# power_supply.net
KiCad netlist of a schematic drawn in Altium Designer
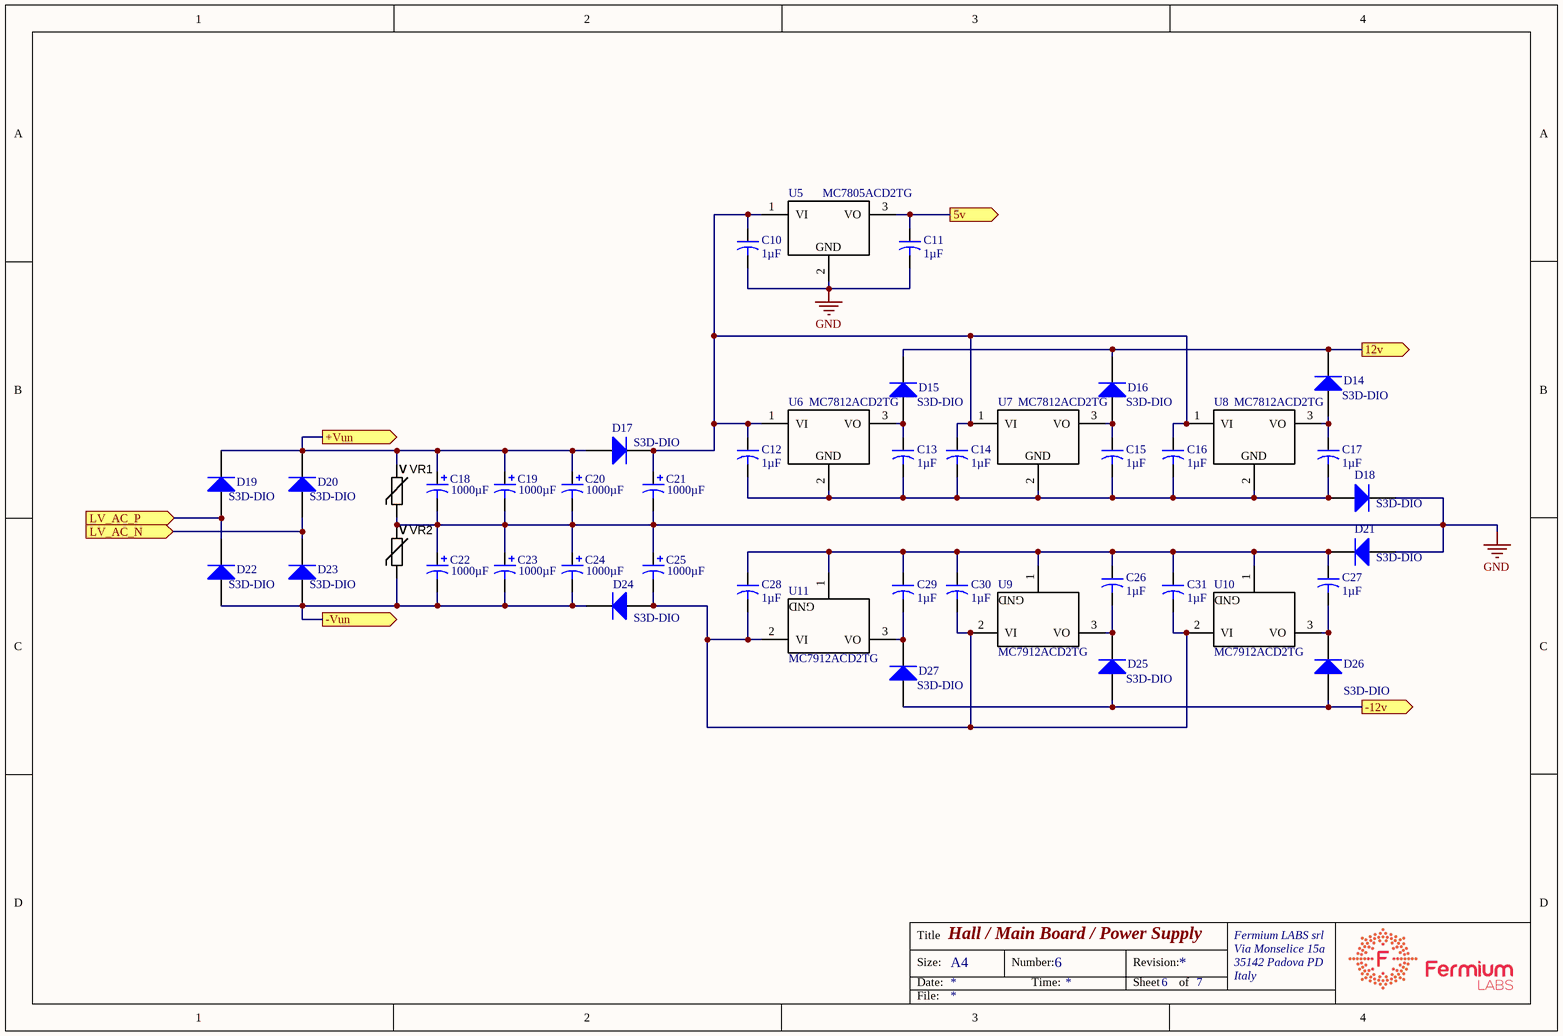
[diagram p0: power_supply.SchDoc]

(export (version "E")
  (design (tool "Eeschema 10.0.6"))
  (components
    (comp (ref "C10")
      (value "~")
      (footprint "Passives:CAP 0805/2012")
      (description "Capacitor")
      (fields
        (field (name "MANUFACTURER") "SAMSUNG")
        (field (name "MANUFACTURER PART NUMBER") "CL21B105KAFNNNE")
        (field (name "CAPACITANCE") "1µF")
        (field (name "PUBLISHER") "Altium Limited")
      )
      (libsource (lib "Miscellaneous Devices") (part "Cap2"))
    )
    (comp (ref "C11")
      (value "~")
      (footprint "Passives:CAP 0805/2012")
      (description "Capacitor")
      (fields
        (field (name "MANUFACTURER") "SAMSUNG")
        (field (name "MANUFACTURER PART NUMBER") "CL21B105KAFNNNE")
        (field (name "CAPACITANCE") "1µF")
        (field (name "PUBLISHER") "Altium Limited")
      )
      (libsource (lib "Miscellaneous Devices") (part "Cap2"))
    )
    (comp (ref "C12")
      (value "~")
      (footprint "Passives:CAP 0805/2012")
      (description "Capacitor")
      (fields
        (field (name "MANUFACTURER") "SAMSUNG")
        (field (name "MANUFACTURER PART NUMBER") "CL21B105KAFNNNE")
        (field (name "CAPACITANCE") "1µF")
        (field (name "PUBLISHER") "Altium Limited")
      )
      (libsource (lib "Miscellaneous Devices") (part "Cap2"))
    )
    (comp (ref "C13")
      (value "~")
      (footprint "Passives:CAP 0805/2012")
      (description "Capacitor")
      (fields
        (field (name "MANUFACTURER") "SAMSUNG")
        (field (name "MANUFACTURER PART NUMBER") "CL21B105KAFNNNE")
        (field (name "CAPACITANCE") "1µF")
        (field (name "PUBLISHER") "Altium Limited")
      )
      (libsource (lib "Miscellaneous Devices") (part "Cap2"))
    )
    (comp (ref "C14")
      (value "~")
      (footprint "Passives:CAP 0805/2012")
      (description "Capacitor")
      (fields
        (field (name "MANUFACTURER") "SAMSUNG")
        (field (name "MANUFACTURER PART NUMBER") "CL21B105KAFNNNE")
        (field (name "CAPACITANCE") "1µF")
        (field (name "PUBLISHER") "Altium Limited")
      )
      (libsource (lib "Miscellaneous Devices") (part "Cap2"))
    )
    (comp (ref "C15")
      (value "~")
      (footprint "Passives:CAP 0805/2012")
      (description "Capacitor")
      (fields
        (field (name "MANUFACTURER") "SAMSUNG")
        (field (name "MANUFACTURER PART NUMBER") "CL21B105KAFNNNE")
        (field (name "CAPACITANCE") "1µF")
        (field (name "PUBLISHER") "Altium Limited")
      )
      (libsource (lib "Miscellaneous Devices") (part "Cap2"))
    )
    (comp (ref "C16")
      (value "~")
      (footprint "Passives:CAP 0805/2012")
      (description "Capacitor")
      (fields
        (field (name "MANUFACTURER") "SAMSUNG")
        (field (name "MANUFACTURER PART NUMBER") "CL21B105KAFNNNE")
        (field (name "CAPACITANCE") "1µF")
        (field (name "PUBLISHER") "Altium Limited")
      )
      (libsource (lib "Miscellaneous Devices") (part "Cap2"))
    )
    (comp (ref "C17")
      (value "~")
      (footprint "Passives:CAP 0805/2012")
      (description "Capacitor")
      (fields
        (field (name "MANUFACTURER") "SAMSUNG")
        (field (name "MANUFACTURER PART NUMBER") "CL21B105KAFNNNE")
        (field (name "CAPACITANCE") "1µF")
        (field (name "PUBLISHER") "Altium Limited")
      )
      (libsource (lib "Miscellaneous Devices") (part "Cap2"))
    )
    (comp (ref "C18")
      (value "~")
      (footprint "PBL - THD Packages:CAPE5.0mm")
      (description "capacitor , electrolytic")
      (fields
        (field (name "MANUFACTURER") "United Chemi-Con")
        (field (name "MANUFACTURER PART NUMBER") "EKYB250ELL102MJ20S")
        (field (name "CAPACITANCE") "1000µF")
      )
      (libsource (lib "Miscellaneous Devices") (part "Cap Pol1"))
    )
    (comp (ref "C19")
      (value "~")
      (footprint "PBL - THD Packages:CAPE5.0mm")
      (description "capacitor , electrolytic")
      (fields
        (field (name "MANUFACTURER") "United Chemi-Con")
        (field (name "MANUFACTURER PART NUMBER") "EKYB250ELL102MJ20S")
        (field (name "CAPACITANCE") "1000µF")
      )
      (libsource (lib "Miscellaneous Devices") (part "Cap Pol1"))
    )
    (comp (ref "C20")
      (value "~")
      (footprint "PBL - THD Packages:CAPE5.0mm")
      (description "capacitor , electrolytic")
      (fields
        (field (name "MANUFACTURER") "United Chemi-Con")
        (field (name "MANUFACTURER PART NUMBER") "EKYB250ELL102MJ20S")
        (field (name "CAPACITANCE") "1000µF")
      )
      (libsource (lib "Miscellaneous Devices") (part "Cap Pol1"))
    )
    (comp (ref "C21")
      (value "~")
      (footprint "PBL - THD Packages:CAPE5.0mm")
      (description "capacitor , electrolytic")
      (fields
        (field (name "MANUFACTURER") "United Chemi-Con")
        (field (name "MANUFACTURER PART NUMBER") "EKYB250ELL102MJ20S")
        (field (name "CAPACITANCE") "1000µF")
      )
      (libsource (lib "Miscellaneous Devices") (part "Cap Pol1"))
    )
    (comp (ref "C22")
      (value "~")
      (footprint "PBL - THD Packages:CAPE5.0mm")
      (description "capacitor , electrolytic")
      (fields
        (field (name "MANUFACTURER") "United Chemi-Con")
        (field (name "MANUFACTURER PART NUMBER") "EKYB250ELL102MJ20S")
        (field (name "CAPACITANCE") "1000µF")
      )
      (libsource (lib "Miscellaneous Devices") (part "Cap Pol1"))
    )
    (comp (ref "C23")
      (value "~")
      (footprint "PBL - THD Packages:CAPE5.0mm")
      (description "capacitor , electrolytic")
      (fields
        (field (name "MANUFACTURER") "United Chemi-Con")
        (field (name "MANUFACTURER PART NUMBER") "EKYB250ELL102MJ20S")
        (field (name "CAPACITANCE") "1000µF")
      )
      (libsource (lib "Miscellaneous Devices") (part "Cap Pol1"))
    )
    (comp (ref "C24")
      (value "~")
      (footprint "PBL - THD Packages:CAPE5.0mm")
      (description "capacitor , electrolytic")
      (fields
        (field (name "MANUFACTURER") "United Chemi-Con")
        (field (name "MANUFACTURER PART NUMBER") "EKYB250ELL102MJ20S")
        (field (name "CAPACITANCE") "1000µF")
      )
      (libsource (lib "Miscellaneous Devices") (part "Cap Pol1"))
    )
    (comp (ref "C25")
      (value "~")
      (footprint "PBL - THD Packages:CAPE5.0mm")
      (description "capacitor , electrolytic")
      (fields
        (field (name "MANUFACTURER") "United Chemi-Con")
        (field (name "MANUFACTURER PART NUMBER") "EKYB250ELL102MJ20S")
        (field (name "CAPACITANCE") "1000µF")
      )
      (libsource (lib "Miscellaneous Devices") (part "Cap Pol1"))
    )
    (comp (ref "C26")
      (value "~")
      (footprint "Passives:CAP 0805/2012")
      (description "Capacitor")
      (fields
        (field (name "MANUFACTURER") "SAMSUNG")
        (field (name "MANUFACTURER PART NUMBER") "CL21B105KAFNNNE")
        (field (name "CAPACITANCE") "1µF")
        (field (name "PUBLISHER") "Altium Limited")
      )
      (libsource (lib "Miscellaneous Devices") (part "Cap2"))
    )
    (comp (ref "C27")
      (value "~")
      (footprint "Passives:CAP 0805/2012")
      (description "Capacitor")
      (fields
        (field (name "MANUFACTURER") "SAMSUNG")
        (field (name "MANUFACTURER PART NUMBER") "CL21B105KAFNNNE")
        (field (name "CAPACITANCE") "1µF")
        (field (name "PUBLISHER") "Altium Limited")
      )
      (libsource (lib "Miscellaneous Devices") (part "Cap2"))
    )
    (comp (ref "C28")
      (value "~")
      (footprint "Passives:CAP 0805/2012")
      (description "Capacitor")
      (fields
        (field (name "MANUFACTURER") "SAMSUNG")
        (field (name "MANUFACTURER PART NUMBER") "CL21B105KAFNNNE")
        (field (name "CAPACITANCE") "1µF")
        (field (name "PUBLISHER") "Altium Limited")
      )
      (libsource (lib "Miscellaneous Devices") (part "Cap2"))
    )
    (comp (ref "C29")
      (value "~")
      (footprint "Passives:CAP 0805/2012")
      (description "Capacitor")
      (fields
        (field (name "MANUFACTURER") "SAMSUNG")
        (field (name "MANUFACTURER PART NUMBER") "CL21B105KAFNNNE")
        (field (name "CAPACITANCE") "1µF")
        (field (name "PUBLISHER") "Altium Limited")
      )
      (libsource (lib "Miscellaneous Devices") (part "Cap2"))
    )
    (comp (ref "C30")
      (value "~")
      (footprint "Passives:CAP 0805/2012")
      (description "Capacitor")
      (fields
        (field (name "MANUFACTURER") "SAMSUNG")
        (field (name "MANUFACTURER PART NUMBER") "CL21B105KAFNNNE")
        (field (name "CAPACITANCE") "1µF")
        (field (name "PUBLISHER") "Altium Limited")
      )
      (libsource (lib "Miscellaneous Devices") (part "Cap2"))
    )
    (comp (ref "C31")
      (value "~")
      (footprint "Passives:CAP 0805/2012")
      (description "Capacitor")
      (fields
        (field (name "MANUFACTURER") "SAMSUNG")
        (field (name "MANUFACTURER PART NUMBER") "CL21B105KAFNNNE")
        (field (name "CAPACITANCE") "1µF")
        (field (name "PUBLISHER") "Altium Limited")
      )
      (libsource (lib "Miscellaneous Devices") (part "Cap2"))
    )
    (comp (ref "D14")
      (value "~")
      (footprint "DIODE-SMC")
      (description "Diode rectifier 1A")
      (fields
        (field (name "SUPPLIER PART NUMBER 1") "S3D-DIO")
        (field (name "MANUFACTURER") "DIOTEC SEMICONDUCTOR")
        (field (name "MANUFACTURER PART NUMBER") "S3D")
      )
      (libsource (lib "Miscellaneous Devices") (part "Diode 1N4007"))
    )
    (comp (ref "D15")
      (value "~")
      (footprint "DIODE-SMC")
      (description "Diode rectifier 1A")
      (fields
        (field (name "SUPPLIER PART NUMBER 1") "S3D-DIO")
        (field (name "MANUFACTURER") "DIOTEC SEMICONDUCTOR")
        (field (name "MANUFACTURER PART NUMBER") "S3D")
      )
      (libsource (lib "Miscellaneous Devices") (part "Diode 1N4007"))
    )
    (comp (ref "D16")
      (value "~")
      (footprint "DIODE-SMC")
      (description "Diode rectifier 1A")
      (fields
        (field (name "SUPPLIER PART NUMBER 1") "S3D-DIO")
        (field (name "MANUFACTURER") "DIOTEC SEMICONDUCTOR")
        (field (name "MANUFACTURER PART NUMBER") "S3D")
      )
      (libsource (lib "Miscellaneous Devices") (part "Diode 1N4007"))
    )
    (comp (ref "D17")
      (value "~")
      (footprint "DIODE-SMC")
      (description "Diode rectifier 1A")
      (fields
        (field (name "SUPPLIER PART NUMBER 1") "S3D-DIO")
        (field (name "MANUFACTURER") "DIOTEC SEMICONDUCTOR")
        (field (name "MANUFACTURER PART NUMBER") "S3D")
      )
      (libsource (lib "Miscellaneous Devices") (part "Diode 1N4007"))
    )
    (comp (ref "D18")
      (value "~")
      (footprint "DIODE-SMC")
      (description "Diode rectifier 1A")
      (fields
        (field (name "SUPPLIER PART NUMBER 1") "S3D-DIO")
        (field (name "MANUFACTURER") "DIOTEC SEMICONDUCTOR")
        (field (name "MANUFACTURER PART NUMBER") "S3D")
      )
      (libsource (lib "Miscellaneous Devices") (part "Diode 1N4007"))
    )
    (comp (ref "D19")
      (value "~")
      (footprint "DIODE-SMC")
      (description "Diode rectifier 1A")
      (fields
        (field (name "SUPPLIER PART NUMBER 1") "S3D-DIO")
        (field (name "MANUFACTURER") "DIOTEC SEMICONDUCTOR")
        (field (name "MANUFACTURER PART NUMBER") "S3D")
      )
      (libsource (lib "Miscellaneous Devices") (part "Diode 1N4007"))
    )
    (comp (ref "D20")
      (value "~")
      (footprint "DIODE-SMC")
      (description "Diode rectifier 1A")
      (fields
        (field (name "SUPPLIER PART NUMBER 1") "S3D-DIO")
        (field (name "MANUFACTURER") "DIOTEC SEMICONDUCTOR")
        (field (name "MANUFACTURER PART NUMBER") "S3D")
      )
      (libsource (lib "Miscellaneous Devices") (part "Diode 1N4007"))
    )
    (comp (ref "D21")
      (value "~")
      (footprint "DIODE-SMC")
      (description "Diode rectifier 1A")
      (fields
        (field (name "SUPPLIER PART NUMBER 1") "S3D-DIO")
        (field (name "MANUFACTURER") "DIOTEC SEMICONDUCTOR")
        (field (name "MANUFACTURER PART NUMBER") "S3D")
      )
      (libsource (lib "Miscellaneous Devices") (part "Diode 1N4007"))
    )
    (comp (ref "D22")
      (value "~")
      (footprint "DIODE-SMC")
      (description "Diode rectifier 1A")
      (fields
        (field (name "SUPPLIER PART NUMBER 1") "S3D-DIO")
        (field (name "MANUFACTURER") "DIOTEC SEMICONDUCTOR")
        (field (name "MANUFACTURER PART NUMBER") "S3D")
      )
      (libsource (lib "Miscellaneous Devices") (part "Diode 1N4007"))
    )
    (comp (ref "D23")
      (value "~")
      (footprint "DIODE-SMC")
      (description "Diode rectifier 1A")
      (fields
        (field (name "SUPPLIER PART NUMBER 1") "S3D-DIO")
        (field (name "MANUFACTURER") "DIOTEC SEMICONDUCTOR")
        (field (name "MANUFACTURER PART NUMBER") "S3D")
      )
      (libsource (lib "Miscellaneous Devices") (part "Diode 1N4007"))
    )
    (comp (ref "D24")
      (value "~")
      (footprint "DIODE-SMC")
      (description "Diode rectifier 1A")
      (fields
        (field (name "SUPPLIER PART NUMBER 1") "S3D-DIO")
        (field (name "MANUFACTURER") "DIOTEC SEMICONDUCTOR")
        (field (name "MANUFACTURER PART NUMBER") "S3D")
      )
      (libsource (lib "Miscellaneous Devices") (part "Diode 1N4007"))
    )
    (comp (ref "D25")
      (value "~")
      (footprint "DIODE-SMC")
      (description "Diode rectifier 1A")
      (fields
        (field (name "SUPPLIER PART NUMBER 1") "S3D-DIO")
        (field (name "MANUFACTURER") "DIOTEC SEMICONDUCTOR")
        (field (name "MANUFACTURER PART NUMBER") "S3D")
      )
      (libsource (lib "Miscellaneous Devices") (part "Diode 1N4007"))
    )
    (comp (ref "D26")
      (value "~")
      (footprint "DIODE-SMC")
      (description "Diode rectifier 1A")
      (fields
        (field (name "SUPPLIER PART NUMBER 1") "S3D-DIO")
        (field (name "MANUFACTURER") "DIOTEC SEMICONDUCTOR")
        (field (name "MANUFACTURER PART NUMBER") "S3D")
      )
      (libsource (lib "Miscellaneous Devices") (part "Diode 1N4007"))
    )
    (comp (ref "D27")
      (value "~")
      (footprint "DIODE-SMC")
      (description "Diode rectifier 1A")
      (fields
        (field (name "SUPPLIER PART NUMBER 1") "S3D-DIO")
        (field (name "MANUFACTURER") "DIOTEC SEMICONDUCTOR")
        (field (name "MANUFACTURER PART NUMBER") "S3D")
      )
      (libsource (lib "Miscellaneous Devices") (part "Diode 1N4007"))
    )
    (comp (ref "U5")
      (value "~")
      (footprint "PBL - SMD Packages:D2PAK-3")
      (description "Voltage regulator, 5V")
      (fields
        (field (name "SUPPLIER PART NUMBER 1") "MC7805ACD2TG")
        (field (name "MANUFACTURER") "ON SEMICONDUCTOR")
        (field (name "MANUFACTURER PART NUMBER") "MC7805ACD2TG")
      )
      (libsource (lib "vh_altium_library") (part "L7805-TO220"))
    )
    (comp (ref "U6")
      (value "~")
      (footprint "PBL - SMD Packages:D2PAK-3")
      (description "Voltage regulator, 15V")
      (fields
        (field (name "SUPPLIER PART NUMBER 1") "MC7812ACD2TG")
        (field (name "MANUFACTURER") "ON SEMICONDUCTOR")
        (field (name "MANUFACTURER PART NUMBER") "MC7812ACD2TG")
      )
      (libsource (lib "vh_altium_library") (part "L7815-TO220"))
    )
    (comp (ref "U7")
      (value "~")
      (footprint "PBL - SMD Packages:D2PAK-3")
      (description "Voltage regulator, 15V")
      (fields
        (field (name "SUPPLIER PART NUMBER 1") "MC7812ACD2TG")
        (field (name "MANUFACTURER") "ON SEMICONDUCTOR")
        (field (name "MANUFACTURER PART NUMBER") "MC7812ACD2TG")
      )
      (libsource (lib "vh_altium_library") (part "L7815-TO220"))
    )
    (comp (ref "U8")
      (value "~")
      (footprint "PBL - SMD Packages:D2PAK-3")
      (description "Voltage regulator, 15V")
      (fields
        (field (name "SUPPLIER PART NUMBER 1") "MC7812ACD2TG")
        (field (name "MANUFACTURER") "ON SEMICONDUCTOR")
        (field (name "MANUFACTURER PART NUMBER") "MC7812ACD2TG")
      )
      (libsource (lib "vh_altium_library") (part "L7815-TO220"))
    )
    (comp (ref "U9")
      (value "~")
      (footprint "PBL - SMD Packages:D2PAK-3")
      (description "Voltage regulator-15.0V")
      (fields
        (field (name "SUPPLIER PART NUMBER 1") "MC7912ACD2TG")
        (field (name "MANUFACTURER") "ON SEMICONDUCTOR")
        (field (name "MANUFACTURER PART NUMBER") "MC7912ACD2TG")
      )
      (libsource (lib "vh_altium_library") (part "L7915-TO220"))
    )
    (comp (ref "U10")
      (value "~")
      (footprint "PBL - SMD Packages:D2PAK-3")
      (description "Voltage regulator-15.0V")
      (fields
        (field (name "SUPPLIER PART NUMBER 1") "MC7912ACD2TG")
        (field (name "MANUFACTURER") "ON SEMICONDUCTOR")
        (field (name "MANUFACTURER PART NUMBER") "MC7912ACD2TG")
      )
      (libsource (lib "vh_altium_library") (part "L7915-TO220"))
    )
    (comp (ref "U11")
      (value "~")
      (footprint "PBL - SMD Packages:D2PAK-3")
      (description "Voltage regulator-15.0V")
      (fields
        (field (name "SUPPLIER PART NUMBER 1") "MC7912ACD2TG")
        (field (name "MANUFACTURER") "ON SEMICONDUCTOR")
        (field (name "MANUFACTURER PART NUMBER") "MC7912ACD2TG")
      )
      (libsource (lib "vh_altium_library") (part "L7915-TO220"))
    )
    (comp (ref "VR1")
      (value "~")
      (footprint "CAP 1206/3216 - 1.8MM")
      (description "Varistor")
      (fields
        (field (name "MANUFACTURER") "EPCOS")
        (field (name "MANUFACTURER PART NUMBER") "B72520T0250K062")
      )
      (libsource (lib "PBL - Fuses and Protection") (part "Varistor_MOV"))
    )
    (comp (ref "VR2")
      (value "~")
      (footprint "CAP 1206/3216 - 1.8MM")
      (description "Varistor")
      (fields
        (field (name "MANUFACTURER") "EPCOS")
        (field (name "MANUFACTURER PART NUMBER") "B72520T0250K062")
      )
      (libsource (lib "PBL - Fuses and Protection") (part "Varistor_MOV"))
    )
  )
  (nets
    (net (code "1") (name "/+Vun") (class "Default")
      (node (ref "C18") (pin "1") (pinfunction "1_1") (pintype "passive"))
      (node (ref "C19") (pin "1") (pinfunction "1_1") (pintype "passive"))
      (node (ref "C20") (pin "1") (pinfunction "1_1") (pintype "passive"))
      (node (ref "D17") (pin "A") (pinfunction "A_A") (pintype "passive"))
      (node (ref "D19") (pin "K") (pinfunction "K_K") (pintype "passive"))
      (node (ref "D20") (pin "K") (pinfunction "K_K") (pintype "passive"))
      (node (ref "VR1") (pin "1") (pinfunction "1_1") (pintype "passive"))
    )
    (net (code "2") (name "/-12v") (class "Default")
      (node (ref "D25") (pin "A") (pinfunction "A_A") (pintype "passive"))
      (node (ref "D26") (pin "A") (pinfunction "A_A") (pintype "passive"))
      (node (ref "D27") (pin "A") (pinfunction "A_A") (pintype "passive"))
    )
    (net (code "3") (name "/-Vun") (class "Default")
      (node (ref "C22") (pin "2") (pinfunction "2_2") (pintype "passive"))
      (node (ref "C23") (pin "2") (pinfunction "2_2") (pintype "passive"))
      (node (ref "C24") (pin "2") (pinfunction "2_2") (pintype "passive"))
      (node (ref "D22") (pin "A") (pinfunction "A_A") (pintype "passive"))
      (node (ref "D23") (pin "A") (pinfunction "A_A") (pintype "passive"))
      (node (ref "D24") (pin "K") (pinfunction "K_K") (pintype "passive"))
      (node (ref "VR2") (pin "2") (pinfunction "2_2") (pintype "passive"))
    )
    (net (code "4") (name "/5v") (class "Default")
      (node (ref "C11") (pin "1") (pinfunction "1_1") (pintype "passive"))
      (node (ref "U5") (pin "3") (pinfunction "VO_3") (pintype "passive"))
    )
    (net (code "5") (name "/12v") (class "Default")
      (node (ref "D14") (pin "K") (pinfunction "K_K") (pintype "passive"))
      (node (ref "D15") (pin "K") (pinfunction "K_K") (pintype "passive"))
      (node (ref "D16") (pin "K") (pinfunction "K_K") (pintype "passive"))
    )
    (net (code "6") (name "/LV_AC_N") (class "Default")
      (node (ref "D20") (pin "A") (pinfunction "A_A") (pintype "passive"))
      (node (ref "D23") (pin "K") (pinfunction "K_K") (pintype "passive"))
    )
    (net (code "7") (name "/LV_AC_P") (class "Default")
      (node (ref "D19") (pin "A") (pinfunction "A_A") (pintype "passive"))
      (node (ref "D22") (pin "K") (pinfunction "K_K") (pintype "passive"))
    )
    (net (code "8") (name "GND") (class "Default")
      (node (ref "C10") (pin "2") (pinfunction "2_2") (pintype "passive"))
      (node (ref "C11") (pin "2") (pinfunction "2_2") (pintype "passive"))
      (node (ref "C18") (pin "2") (pinfunction "2_2") (pintype "passive"))
      (node (ref "C19") (pin "2") (pinfunction "2_2") (pintype "passive"))
      (node (ref "C20") (pin "2") (pinfunction "2_2") (pintype "passive"))
      (node (ref "C21") (pin "2") (pinfunction "2_2") (pintype "passive"))
      (node (ref "C22") (pin "1") (pinfunction "1_1") (pintype "passive"))
      (node (ref "C23") (pin "1") (pinfunction "1_1") (pintype "passive"))
      (node (ref "C24") (pin "1") (pinfunction "1_1") (pintype "passive"))
      (node (ref "C25") (pin "1") (pinfunction "1_1") (pintype "passive"))
      (node (ref "D18") (pin "K") (pinfunction "K_K") (pintype "passive"))
      (node (ref "D21") (pin "A") (pinfunction "A_A") (pintype "passive"))
      (node (ref "U5") (pin "2") (pintype "passive"))
      (node (ref "VR1") (pin "2") (pinfunction "2_2") (pintype "passive"))
      (node (ref "VR2") (pin "1") (pinfunction "1_1") (pintype "passive"))
    )
    (net (code "9") (name "Net-(C12-Pad2)") (class "Default")
      (node (ref "C12") (pin "2") (pinfunction "2_2") (pintype "passive"))
      (node (ref "C13") (pin "2") (pinfunction "2_2") (pintype "passive"))
      (node (ref "C14") (pin "2") (pinfunction "2_2") (pintype "passive"))
      (node (ref "C15") (pin "2") (pinfunction "2_2") (pintype "passive"))
      (node (ref "C16") (pin "2") (pinfunction "2_2") (pintype "passive"))
      (node (ref "C17") (pin "2") (pinfunction "2_2") (pintype "passive"))
      (node (ref "D18") (pin "A") (pinfunction "A_A") (pintype "passive"))
      (node (ref "U6") (pin "2") (pintype "passive"))
      (node (ref "U7") (pin "2") (pintype "passive"))
      (node (ref "U8") (pin "2") (pintype "passive"))
    )
    (net (code "10") (name "Net-(C26-Pad1)") (class "Default")
      (node (ref "C26") (pin "1") (pinfunction "1_1") (pintype "passive"))
      (node (ref "C27") (pin "1") (pinfunction "1_1") (pintype "passive"))
      (node (ref "C28") (pin "1") (pinfunction "1_1") (pintype "passive"))
      (node (ref "C29") (pin "1") (pinfunction "1_1") (pintype "passive"))
      (node (ref "C30") (pin "1") (pinfunction "1_1") (pintype "passive"))
      (node (ref "C31") (pin "1") (pinfunction "1_1") (pintype "passive"))
      (node (ref "D21") (pin "K") (pinfunction "K_K") (pintype "passive"))
      (node (ref "U10") (pin "1") (pintype "passive"))
      (node (ref "U11") (pin "1") (pintype "passive"))
      (node (ref "U9") (pin "1") (pintype "passive"))
    )
    (net (code "11") (name "Net-(U5-VI)") (class "Default")
      (node (ref "C10") (pin "1") (pinfunction "1_1") (pintype "passive"))
      (node (ref "C12") (pin "1") (pinfunction "1_1") (pintype "passive"))
      (node (ref "C14") (pin "1") (pinfunction "1_1") (pintype "passive"))
      (node (ref "C16") (pin "1") (pinfunction "1_1") (pintype "passive"))
      (node (ref "C21") (pin "1") (pinfunction "1_1") (pintype "passive"))
      (node (ref "D17") (pin "K") (pinfunction "K_K") (pintype "passive"))
      (node (ref "U5") (pin "1") (pinfunction "VI_1") (pintype "passive"))
      (node (ref "U6") (pin "1") (pinfunction "VI_1") (pintype "passive"))
      (node (ref "U7") (pin "1") (pinfunction "VI_1") (pintype "passive"))
      (node (ref "U8") (pin "1") (pinfunction "VI_1") (pintype "passive"))
    )
    (net (code "12") (name "Net-(U6-VO)") (class "Default")
      (node (ref "C13") (pin "1") (pinfunction "1_1") (pintype "passive"))
      (node (ref "D15") (pin "A") (pinfunction "A_A") (pintype "passive"))
      (node (ref "U6") (pin "3") (pinfunction "VO_3") (pintype "passive"))
    )
    (net (code "13") (name "Net-(U7-VO)") (class "Default")
      (node (ref "C15") (pin "1") (pinfunction "1_1") (pintype "passive"))
      (node (ref "D16") (pin "A") (pinfunction "A_A") (pintype "passive"))
      (node (ref "U7") (pin "3") (pinfunction "VO_3") (pintype "passive"))
    )
    (net (code "14") (name "Net-(U8-VO)") (class "Default")
      (node (ref "C17") (pin "1") (pinfunction "1_1") (pintype "passive"))
      (node (ref "D14") (pin "A") (pinfunction "A_A") (pintype "passive"))
      (node (ref "U8") (pin "3") (pinfunction "VO_3") (pintype "passive"))
    )
    (net (code "15") (name "Net-(U9-VO)") (class "Default")
      (node (ref "C26") (pin "2") (pinfunction "2_2") (pintype "passive"))
      (node (ref "D25") (pin "K") (pinfunction "K_K") (pintype "passive"))
      (node (ref "U9") (pin "3") (pinfunction "VO_3") (pintype "passive"))
    )
    (net (code "16") (name "Net-(U10-VI)") (class "Default")
      (node (ref "C25") (pin "2") (pinfunction "2_2") (pintype "passive"))
      (node (ref "C28") (pin "2") (pinfunction "2_2") (pintype "passive"))
      (node (ref "C30") (pin "2") (pinfunction "2_2") (pintype "passive"))
      (node (ref "C31") (pin "2") (pinfunction "2_2") (pintype "passive"))
      (node (ref "D24") (pin "A") (pinfunction "A_A") (pintype "passive"))
      (node (ref "U10") (pin "2") (pinfunction "VI_2") (pintype "passive"))
      (node (ref "U11") (pin "2") (pinfunction "VI_2") (pintype "passive"))
      (node (ref "U9") (pin "2") (pinfunction "VI_2") (pintype "passive"))
    )
    (net (code "17") (name "Net-(U10-VO)") (class "Default")
      (node (ref "C27") (pin "2") (pinfunction "2_2") (pintype "passive"))
      (node (ref "D26") (pin "K") (pinfunction "K_K") (pintype "passive"))
      (node (ref "U10") (pin "3") (pinfunction "VO_3") (pintype "passive"))
    )
    (net (code "18") (name "Net-(U11-VO)") (class "Default")
      (node (ref "C29") (pin "2") (pinfunction "2_2") (pintype "passive"))
      (node (ref "D27") (pin "K") (pinfunction "K_K") (pintype "passive"))
      (node (ref "U11") (pin "3") (pinfunction "VO_3") (pintype "passive"))
    )
  )
)
